# AnyFridge.net
KiCad netlist of a schematic drawn in EAGLE
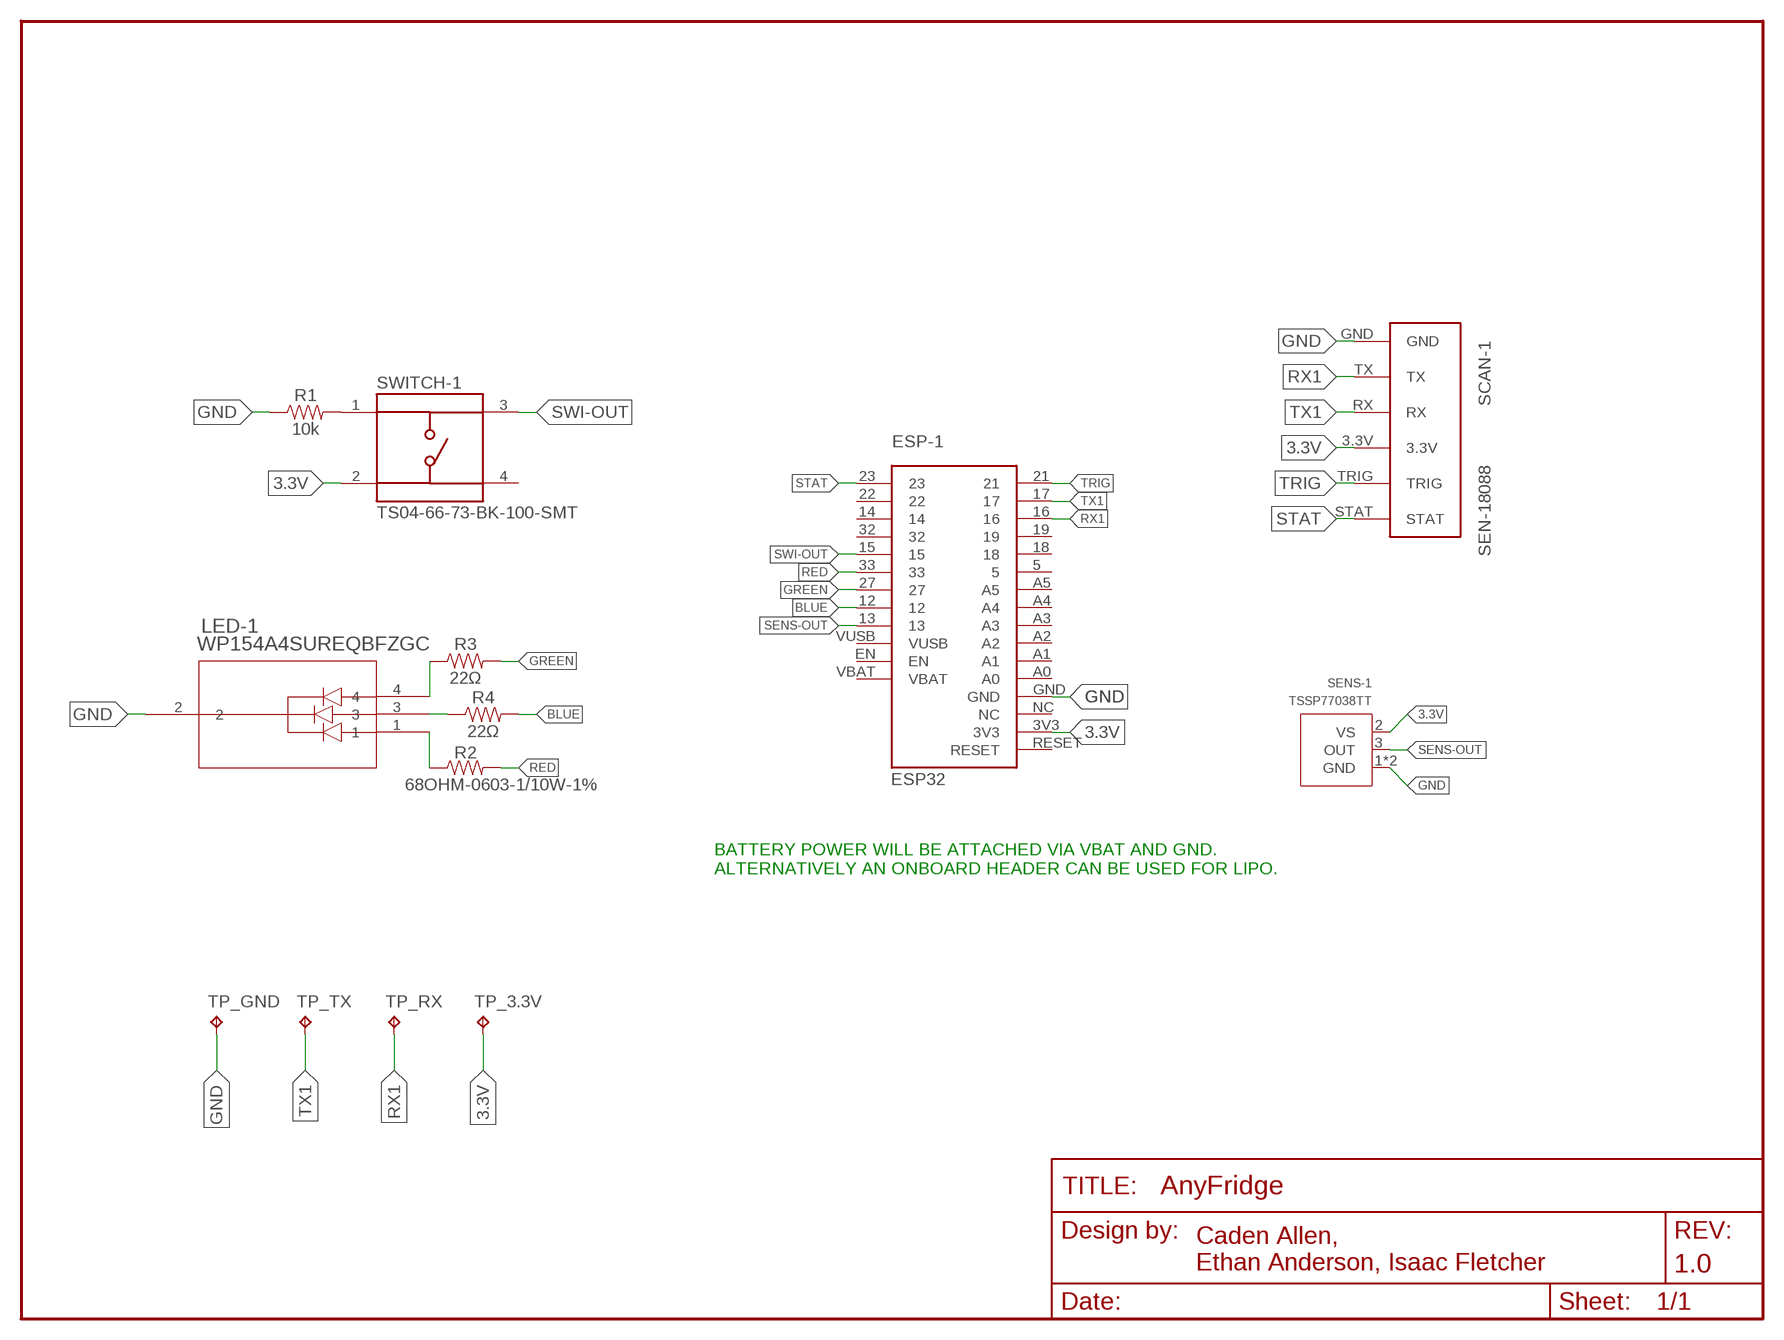
[diagram p0: schematic, sheet 1]

(export (version "E")
  (design (tool "Eeschema 10.0.6"))
  (components
    (comp (ref "ESP-1")
      (value "ESP32")
      (footprint "eagle-import:ESP32")
      (libsource (lib "eagle-import") (part "ESP32"))
    )
    (comp (ref "FRAME1")
      (value "FRAME-LETTERNO_PACKAGE")
      (footprint "eagle-import:DUMMY")
      (fields (field (name "DESIGNER") "Nobody"))
      (libsource (lib "eagle-import") (part "FRAME-LETTERNO_PACKAGE"))
    )
    (comp (ref "LED-1")
      (value "WP154A4SUREQBFZGC")
      (footprint "eagle-import:LED4_WP154A4SUREQBFZGC_KNB")
      (fields (field (name "COPYRIGHT") "Copyright (C) 2025 Ultra Librarian. All rights reserved."))
      (libsource (lib "eagle-import") (part "WP154A4SUREQBFZGC"))
    )
    (comp (ref "R1")
      (value "10k")
      (footprint "eagle-import:AXIAL-0.3")
      (libsource (lib "eagle-import") (part "10KOHM-HORIZ-1/4W-1%"))
    )
    (comp (ref "R2")
      (value "68OHM-0603-1/10W-1%")
      (footprint "eagle-import:0603")
      (libsource (lib "eagle-import") (part "68OHM-0603-1/10W-1%"))
    )
    (comp (ref "R3")
      (value "22Ω")
      (footprint "eagle-import:0603")
      (libsource (lib "eagle-import") (part "22OHM-0603-1/10W-1%"))
    )
    (comp (ref "R4")
      (value "22Ω")
      (footprint "eagle-import:0603")
      (libsource (lib "eagle-import") (part "22OHM-0603-1/10W-1%"))
    )
    (comp (ref "SCAN-1")
      (value "SEN-18088")
      (footprint "eagle-import:SEN-18088")
      (libsource (lib "eagle-import") (part "SEN-18088"))
    )
    (comp (ref "SENS-1")
      (value "TSSP77038TT")
      (footprint "eagle-import:TSSP77038TT")
      (fields (field (name "MF") "Vishay"))
      (libsource (lib "eagle-import") (part "TSSP77038TT"))
    )
    (comp (ref "SWITCH-1")
      (value "TS04-66-73-BK-100-SMT")
      (footprint "eagle-import:SW_TS04-66-73-BK-100-SMT")
      (fields (field (name "MANUFACTURER") "CUI Devices"))
      (libsource (lib "eagle-import") (part "TS04-66-73-BK-100-SMT"))
    )
    (comp (ref "TP_3.3V")
      (value "TPPAD1-13")
      (footprint "eagle-import:P1-13")
      (libsource (lib "eagle-import") (part "TPPAD1-13"))
    )
    (comp (ref "TP_GND")
      (value "TPPAD1-13")
      (footprint "eagle-import:P1-13")
      (libsource (lib "eagle-import") (part "TPPAD1-13"))
    )
    (comp (ref "TP_RX")
      (value "TPPAD1-13")
      (footprint "eagle-import:P1-13")
      (libsource (lib "eagle-import") (part "TPPAD1-13"))
    )
    (comp (ref "TP_TX")
      (value "TPPAD1-13")
      (footprint "eagle-import:P1-13")
      (libsource (lib "eagle-import") (part "TPPAD1-13"))
    )
  )
  (nets
    (net (code "1") (name "3.3V") (class "Default")
      (node (ref "ESP-1") (pin "3V3") (pinfunction "3V3_3V3") (pintype "bidirectional"))
      (node (ref "SCAN-1") (pin "3.3V") (pinfunction "3.3V_3.3V") (pintype "bidirectional"))
      (node (ref "SENS-1") (pin "2") (pinfunction "VS_2") (pintype "bidirectional"))
      (node (ref "SWITCH-1") (pin "2") (pinfunction "2_2") (pintype "passive"))
      (node (ref "TP_3.3V") (pin "TP") (pinfunction "TP_TP") (pintype "input"))
    )
    (net (code "2") (name "BLUE") (class "Default")
      (node (ref "ESP-1") (pin "12") (pinfunction "12_12") (pintype "bidirectional"))
      (node (ref "R4") (pin "2") (pinfunction "2_2") (pintype "passive"))
    )
    (net (code "3") (name "GND") (class "Default")
      (node (ref "ESP-1") (pin "GND") (pinfunction "GND_GND") (pintype "bidirectional"))
      (node (ref "LED-1") (pin "2") (pinfunction "2_2") (pintype "passive"))
      (node (ref "R1") (pin "P$1") (pinfunction "1_P$1") (pintype "passive"))
      (node (ref "SCAN-1") (pin "GND") (pinfunction "GND_GND") (pintype "bidirectional"))
      (node (ref "SENS-1") (pin "1") (pinfunction "GND_1") (pintype "bidirectional"))
      (node (ref "SENS-1") (pin "4") (pinfunction "GND_4") (pintype "bidirectional"))
      (node (ref "TP_GND") (pin "TP") (pinfunction "TP_TP") (pintype "input"))
    )
    (net (code "4") (name "GREEN") (class "Default")
      (node (ref "ESP-1") (pin "27") (pinfunction "27_27") (pintype "bidirectional"))
      (node (ref "R3") (pin "2") (pinfunction "2_2") (pintype "passive"))
    )
    (net (code "5") (name "Net-(LED-1-Pad1)") (class "Default")
      (node (ref "LED-1") (pin "1") (pinfunction "1_1") (pintype "passive"))
      (node (ref "R2") (pin "1") (pinfunction "1_1") (pintype "passive"))
    )
    (net (code "6") (name "Net-(LED-1-Pad3)") (class "Default")
      (node (ref "LED-1") (pin "3") (pinfunction "3_3") (pintype "passive"))
      (node (ref "R4") (pin "1") (pinfunction "1_1") (pintype "passive"))
    )
    (net (code "7") (name "Net-(LED-1-Pad4)") (class "Default")
      (node (ref "LED-1") (pin "4") (pinfunction "4_4") (pintype "passive"))
      (node (ref "R3") (pin "1") (pinfunction "1_1") (pintype "passive"))
    )
    (net (code "8") (name "Net-(R1-2)") (class "Default")
      (node (ref "R1") (pin "P$2") (pinfunction "2_P$2") (pintype "passive"))
      (node (ref "SWITCH-1") (pin "1") (pinfunction "1_1") (pintype "passive"))
    )
    (net (code "9") (name "RED") (class "Default")
      (node (ref "ESP-1") (pin "33") (pinfunction "33_33") (pintype "bidirectional"))
      (node (ref "R2") (pin "2") (pinfunction "2_2") (pintype "passive"))
    )
    (net (code "10") (name "RX1") (class "Default")
      (node (ref "ESP-1") (pin "16") (pinfunction "16_16") (pintype "bidirectional"))
      (node (ref "SCAN-1") (pin "TX") (pinfunction "TX_TX") (pintype "bidirectional"))
      (node (ref "TP_RX") (pin "TP") (pinfunction "TP_TP") (pintype "input"))
    )
    (net (code "11") (name "SENS-OUT") (class "Default")
      (node (ref "ESP-1") (pin "13") (pinfunction "13_13") (pintype "bidirectional"))
      (node (ref "SENS-1") (pin "3") (pinfunction "OUT_3") (pintype "bidirectional"))
    )
    (net (code "12") (name "STAT") (class "Default")
      (node (ref "ESP-1") (pin "23") (pinfunction "23_23") (pintype "bidirectional"))
      (node (ref "SCAN-1") (pin "STAT") (pinfunction "STAT_STAT") (pintype "bidirectional"))
    )
    (net (code "13") (name "SWI-OUT") (class "Default")
      (node (ref "ESP-1") (pin "15") (pinfunction "15_15") (pintype "bidirectional"))
      (node (ref "SWITCH-1") (pin "3") (pinfunction "3_3") (pintype "passive"))
    )
    (net (code "14") (name "TRIG") (class "Default")
      (node (ref "ESP-1") (pin "21") (pinfunction "21_21") (pintype "bidirectional"))
      (node (ref "SCAN-1") (pin "TRIG") (pinfunction "TRIG_TRIG") (pintype "bidirectional"))
    )
    (net (code "15") (name "TX1") (class "Default")
      (node (ref "ESP-1") (pin "17") (pinfunction "17_17") (pintype "bidirectional"))
      (node (ref "SCAN-1") (pin "RX") (pinfunction "RX_RX") (pintype "bidirectional"))
      (node (ref "TP_TX") (pin "TP") (pinfunction "TP_TP") (pintype "input"))
    )
    (net (code "16") (name "unconnected-(ESP-1-Pad5)") (class "Default")
      (node (ref "ESP-1") (pin "5") (pinfunction "5_5") (pintype "bidirectional"))
    )
    (net (code "17") (name "unconnected-(ESP-1-Pad14)") (class "Default")
      (node (ref "ESP-1") (pin "14") (pinfunction "14_14") (pintype "bidirectional"))
    )
    (net (code "18") (name "unconnected-(ESP-1-Pad18)") (class "Default")
      (node (ref "ESP-1") (pin "18") (pinfunction "18_18") (pintype "bidirectional"))
    )
    (net (code "19") (name "unconnected-(ESP-1-Pad19)") (class "Default")
      (node (ref "ESP-1") (pin "19") (pinfunction "19_19") (pintype "bidirectional"))
    )
    (net (code "20") (name "unconnected-(ESP-1-Pad22)") (class "Default")
      (node (ref "ESP-1") (pin "22") (pinfunction "22_22") (pintype "bidirectional"))
    )
    (net (code "21") (name "unconnected-(ESP-1-Pad32)") (class "Default")
      (node (ref "ESP-1") (pin "32") (pinfunction "32_32") (pintype "bidirectional"))
    )
    (net (code "22") (name "unconnected-(ESP-1-PadA0)") (class "Default")
      (node (ref "ESP-1") (pin "A0") (pinfunction "A0_A0") (pintype "bidirectional"))
    )
    (net (code "23") (name "unconnected-(ESP-1-PadA1)") (class "Default")
      (node (ref "ESP-1") (pin "A1") (pinfunction "A1_A1") (pintype "bidirectional"))
    )
    (net (code "24") (name "unconnected-(ESP-1-PadA2)") (class "Default")
      (node (ref "ESP-1") (pin "A2") (pinfunction "A2_A2") (pintype "bidirectional"))
    )
    (net (code "25") (name "unconnected-(ESP-1-PadA3)") (class "Default")
      (node (ref "ESP-1") (pin "A3") (pinfunction "A3_A3") (pintype "bidirectional"))
    )
    (net (code "26") (name "unconnected-(ESP-1-PadA4)") (class "Default")
      (node (ref "ESP-1") (pin "A4") (pinfunction "A4_A4") (pintype "bidirectional"))
    )
    (net (code "27") (name "unconnected-(ESP-1-PadA5)") (class "Default")
      (node (ref "ESP-1") (pin "A5") (pinfunction "A5_A5") (pintype "bidirectional"))
    )
    (net (code "28") (name "unconnected-(ESP-1-PadEN)") (class "Default")
      (node (ref "ESP-1") (pin "EN") (pinfunction "EN_EN") (pintype "bidirectional"))
    )
    (net (code "29") (name "unconnected-(ESP-1-PadNC)") (class "Default")
      (node (ref "ESP-1") (pin "NC") (pinfunction "NC_NC") (pintype "bidirectional"))
    )
    (net (code "30") (name "unconnected-(ESP-1-PadRESET)") (class "Default")
      (node (ref "ESP-1") (pin "RESET") (pinfunction "RESET_RESET") (pintype "bidirectional"))
    )
    (net (code "31") (name "unconnected-(ESP-1-PadVBAT)") (class "Default")
      (node (ref "ESP-1") (pin "VBAT") (pinfunction "VBAT_VBAT") (pintype "bidirectional"))
    )
    (net (code "32") (name "unconnected-(ESP-1-PadVUSB)") (class "Default")
      (node (ref "ESP-1") (pin "VUSB") (pinfunction "VUSB_VUSB") (pintype "bidirectional"))
    )
    (net (code "33") (name "unconnected-(SWITCH-1-Pad4)") (class "Default")
      (node (ref "SWITCH-1") (pin "4") (pinfunction "4_4") (pintype "passive"))
    )
  )
)
